# main.net
KiCad netlist of a schematic drawn in Altium Designer
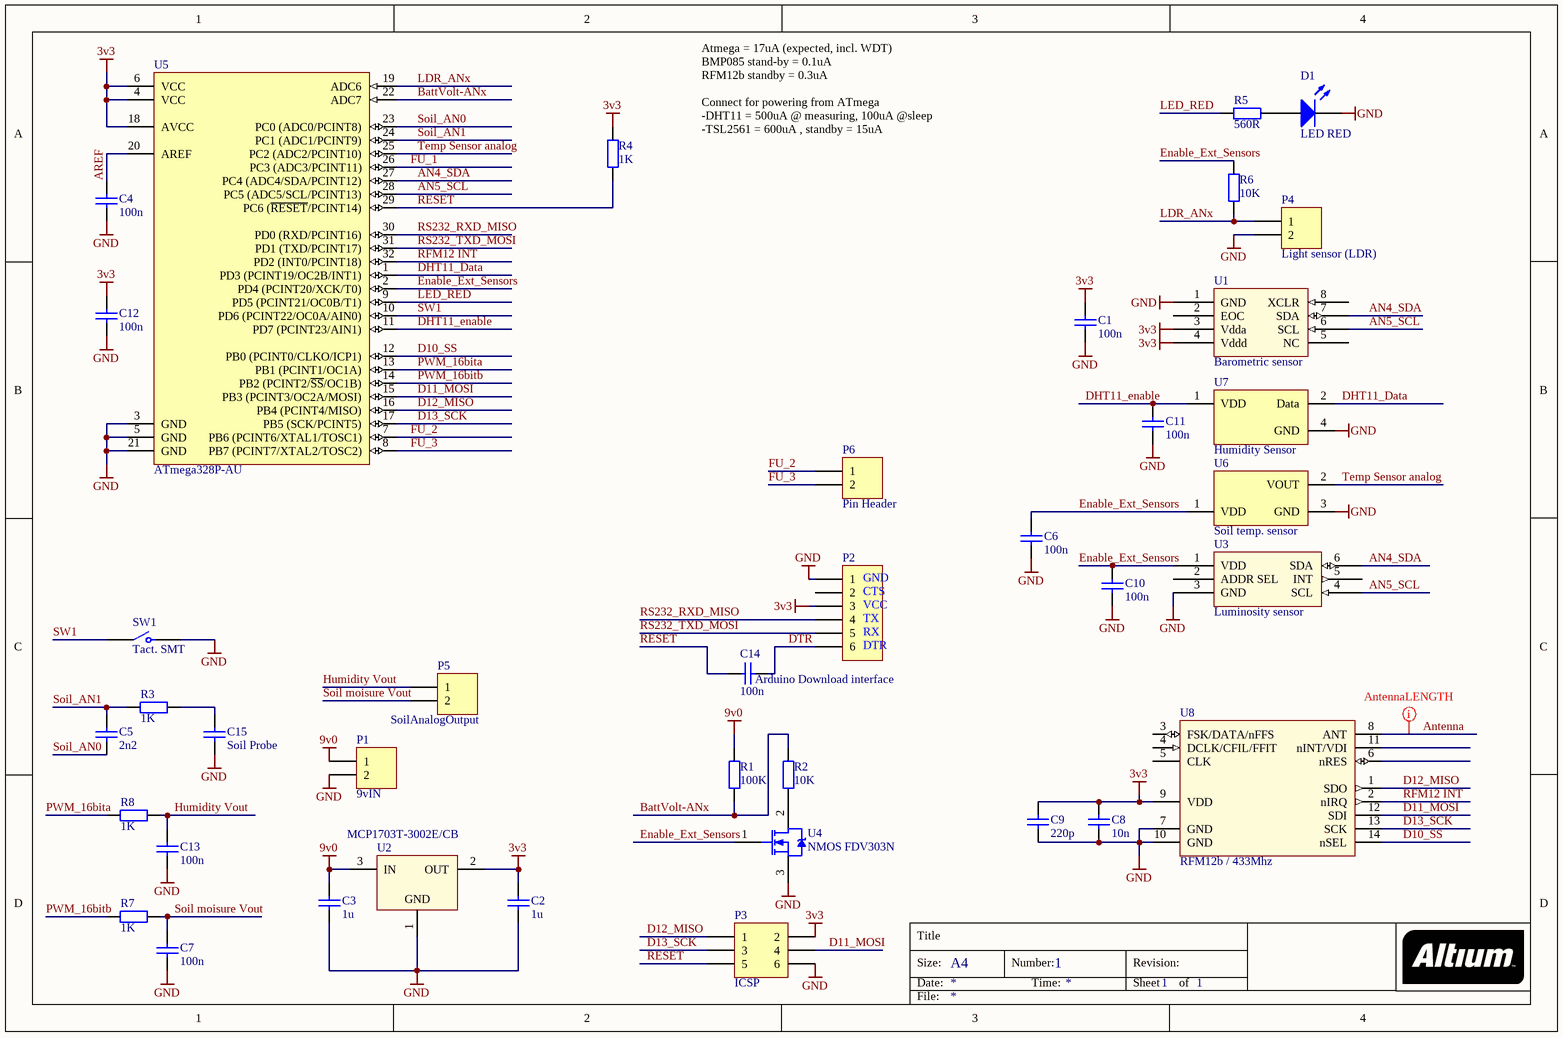
[diagram p0: main.SchDoc]

(export (version "E")
  (design (tool "Eeschema 10.0.6"))
  (components
    (comp (ref "C1") (value "100n") (footprint "C0805") (libsource (lib "OurDb") (part "cap_NonPolar")))
    (comp (ref "C2") (value "1u") (footprint "C0805") (libsource (lib "OurDb") (part "cap_NonPolar")))
    (comp (ref "C3") (value "1u") (footprint "C0805") (libsource (lib "OurDb") (part "cap_NonPolar")))
    (comp (ref "C4") (value "100n") (footprint "C0805") (libsource (lib "OurDb") (part "cap_NonPolar")))
    (comp (ref "C5") (value "2n2") (footprint "C0805") (libsource (lib "OurDb") (part "cap_NonPolar")))
    (comp (ref "C6") (value "100n") (footprint "C0805") (libsource (lib "OurDb") (part "cap_NonPolar")))
    (comp (ref "C7") (value "100n") (footprint "C0805") (libsource (lib "OurDb") (part "cap_NonPolar")))
    (comp (ref "C8") (value "10n") (footprint "C0805") (libsource (lib "OurDb") (part "cap_NonPolar")))
    (comp (ref "C9") (value "220p") (footprint "C0805") (libsource (lib "OurDb") (part "cap_NonPolar")))
    (comp (ref "C10") (value "100n") (footprint "C0805") (libsource (lib "OurDb") (part "cap_NonPolar")))
    (comp (ref "C11") (value "100n") (footprint "C0805") (libsource (lib "OurDb") (part "cap_NonPolar")))
    (comp (ref "C12") (value "100n") (footprint "C0805") (libsource (lib "OurDb") (part "cap_NonPolar")))
    (comp (ref "C13") (value "100n") (footprint "C0805") (libsource (lib "OurDb") (part "cap_NonPolar")))
    (comp (ref "C14") (value "100n") (footprint "C0805") (libsource (lib "OurDb") (part "cap_NonPolar")))
    (comp (ref "C15")
      (value "Soil Probe")
      (footprint "C0805")
      (fields (field (name "PART NUMBER") "18p"))
      (libsource (lib "OurDb") (part "cap_NonPolar"))
    )
    (comp (ref "D1")
      (value "LED RED")
      (footprint "LED-3mm")
      (description "LED, Surface Mount LED Indicator")
      (fields (field (name "PART NUMBER") "Red-3mm"))
      (libsource (lib "OurDb") (part "LED_SINGLE"))
    )
    (comp (ref "P1")
      (value "9vIN")
      (footprint "PH1x2_2.54")
      (description "Con1x2")
      (fields (field (name "PART NUMBER") "PH1x2"))
      (libsource (lib "OurDb") (part "Con1x2"))
    )
    (comp (ref "P2")
      (value "Arduino Download interface")
      (footprint "PH1x6_2.54")
      (description "Con1x6")
      (fields (field (name "PART NUMBER") "PH1x6"))
      (libsource (lib "OurDb") (part "Con1x6"))
    )
    (comp (ref "P3")
      (value "ICSP")
      (footprint "PH2x3_2.54")
      (description "Header, 3-Pin, Dual row")
      (fields (field (name "PART NUMBER") "PH2x3"))
      (libsource (lib "OurDb") (part "Con2x3"))
    )
    (comp (ref "P4")
      (value "Light sensor (LDR)")
      (footprint "PH1x2_2.54")
      (description "Con1x2")
      (fields (field (name "PART NUMBER") "PH1x2"))
      (libsource (lib "OurDb") (part "Con1x2"))
    )
    (comp (ref "P5")
      (value "SoilAnalogOutput")
      (footprint "PH1x2_2.54")
      (description "Con1x2")
      (fields (field (name "PART NUMBER") "PH1x2"))
      (libsource (lib "OurDb") (part "Con1x2"))
    )
    (comp (ref "P6")
      (value "Pin Header")
      (footprint "PH1x2_2.54")
      (description "Con1x2")
      (fields (field (name "PART NUMBER") "PH1x2") (field (name "AUTHOR") "Willy Pietersz"))
      (libsource (lib "OurDb") (part "Con1x2"))
    )
    (comp (ref "R1")
      (value "RESISTOR")
      (footprint "R0805")
      (description "Resistor")
      (fields (field (name "PART NUMBER") "100K") (field (name "PUBLISHER") "Altium Limited"))
      (libsource (lib "") (part "RESISTOR_1"))
    )
    (comp (ref "R2")
      (value "RESISTOR")
      (footprint "R0805")
      (description "Resistor")
      (fields (field (name "PART NUMBER") "10K") (field (name "PUBLISHER") "Altium Limited"))
      (libsource (lib "OurDb") (part "RESISTOR"))
    )
    (comp (ref "R3")
      (value "RESISTOR")
      (footprint "R0805")
      (description "Resistor")
      (fields (field (name "PART NUMBER") "1K") (field (name "PUBLISHER") "Altium Limited"))
      (libsource (lib "") (part "RESISTOR_2"))
    )
    (comp (ref "R4")
      (value "RESISTOR")
      (footprint "R0805")
      (description "Resistor")
      (fields (field (name "PART NUMBER") "1K") (field (name "PUBLISHER") "Altium Limited"))
      (libsource (lib "") (part "RESISTOR_1"))
    )
    (comp (ref "R5")
      (value "RESISTOR")
      (footprint "R0805")
      (description "Resistor")
      (fields (field (name "PART NUMBER") "560R") (field (name "PUBLISHER") "Altium Limited"))
      (libsource (lib "") (part "RESISTOR_3"))
    )
    (comp (ref "R6")
      (value "RESISTOR")
      (footprint "R0805")
      (description "Resistor")
      (fields (field (name "PART NUMBER") "10K") (field (name "PUBLISHER") "Altium Limited"))
      (libsource (lib "") (part "RESISTOR_1"))
    )
    (comp (ref "R7")
      (value "RESISTOR")
      (footprint "R0805")
      (description "Resistor")
      (fields (field (name "PART NUMBER") "1K") (field (name "PUBLISHER") "Altium Limited"))
      (libsource (lib "") (part "RESISTOR_2"))
    )
    (comp (ref "R8")
      (value "RESISTOR")
      (footprint "R0805")
      (description "Resistor")
      (fields (field (name "PART NUMBER") "1K") (field (name "PUBLISHER") "Altium Limited"))
      (libsource (lib "") (part "RESISTOR_2"))
    )
    (comp (ref "SW1")
      (value "Tact. SMT")
      (footprint "Switch TACT 3.5*6")
      (description "Switch")
      (fields
        (field (name "PART NUMBER") "Pushbutton TACT mini 3.5x6")
        (field (name "VOLTAGE") "42")
        (field (name "AUTHOR") "Willem Pietersz")
      )
      (libsource (lib "OurDb") (part "SW-TACT 2p"))
    )
    (comp (ref "U1")
      (value "Barometric sensor")
      (footprint "BMP085")
      (description "Sensor, Barometric")
      (fields (field (name "PART NUMBER") "BMP085"))
      (libsource (lib "OurDb") (part "BMP085"))
    )
    (comp (ref "U2")
      (value "MCP1703T")
      (footprint "SOT23")
      (description "Regulator, 5v")
      (fields (field (name "PART NUMBER") "MCP1703T-3002E/CB"))
      (libsource (lib "OurDb") (part "AMS1117"))
    )
    (comp (ref "U3")
      (value "Luminosity sensor")
      (footprint "TSL2561")
      (description "Sensor, Illumination")
      (fields (field (name "PART NUMBER") "TSL2561"))
      (libsource (lib "OurDb") (part "TSL2561"))
    )
    (comp (ref "U4")
      (value "NMOS FDV303N")
      (footprint "SOT-23-FET")
      (description "Transistor")
      (fields (field (name "PART NUMBER") "FDV303N"))
      (libsource (lib "OurDb") (part "NMOS"))
    )
    (comp (ref "U5")
      (value "ATmega328P-AU")
      (footprint "atmel_32A_N")
      (fields (field (name "PUBLISHER") "Altium Limited"))
      (libsource (lib "AltiumDatabaseSelection") (part "ATmega328P-AU"))
    )
    (comp (ref "U6")
      (value "Soil temp. sensor")
      (footprint "SOT-23-TT3_M")
      (description "Low-Power Linear Active Thermistor IC, 3-Pin SOT-23, Extended Temperature, Tape and Reel")
      (fields (field (name "PART NUMBER") "MCP9700AT-E/TT"))
      (libsource (lib "OurDb") (part "MCP9700AT-E/TT"))
    )
    (comp (ref "U7")
      (value "Humidity Sensor")
      (footprint "DHTXX")
      (description "Humidity / Temp Sensor")
      (fields (field (name "PART NUMBER") "DHT11"))
      (libsource (lib "OurDb") (part "DHT11"))
    )
    (comp (ref "U8")
      (value "RFM12b / 433Mhz")
      (footprint "RFM12_dev")
      (description "Wireless, Transceiver")
      (fields (field (name "PART NUMBER") "RFM12b"))
      (libsource (lib "OurDb") (part "RFM12B"))
    )
  )
  (nets
    (net (code "1") (name "/AN4_SDA") (class "Default")
      (node (ref "U1") (pin "7") (pinfunction "SDA_7") (pintype "bidirectional"))
      (node (ref "U3") (pin "6") (pinfunction "SDA_6") (pintype "bidirectional"))
      (node (ref "U5") (pin "27") (pinfunction "PC4_(ADC4/SDA/PCINT12)_27") (pintype "bidirectional"))
    )
    (net (code "2") (name "/AN5_SCL") (class "Default")
      (node (ref "U1") (pin "6") (pinfunction "SCL_6") (pintype "input"))
      (node (ref "U3") (pin "4") (pinfunction "SCL_4") (pintype "input"))
      (node (ref "U5") (pin "28") (pinfunction "PC5_(ADC5/SCL/PCINT13)_28") (pintype "bidirectional"))
    )
    (net (code "3") (name "/AREF") (class "Default")
      (node (ref "C4") (pin "2") (pinfunction "2_2") (pintype "passive"))
      (node (ref "U5") (pin "20") (pinfunction "AREF_20") (pintype "passive"))
    )
    (net (code "4") (name "/Antenna") (class "Default")
      (node (ref "U8") (pin "8") (pinfunction "ANT_8") (pintype "power_in"))
    )
    (net (code "5") (name "/BattVolt-ANx") (class "Default")
      (node (ref "R1") (pin "2") (pinfunction "2_2") (pintype "passive"))
      (node (ref "R2") (pin "2") (pinfunction "2_2") (pintype "passive"))
      (node (ref "U5") (pin "22") (pinfunction "ADC7_22") (pintype "input"))
    )
    (net (code "6") (name "/D10_SS") (class "Default")
      (node (ref "U5") (pin "12") (pinfunction "PB0_(PCINT0/CLKO/ICP1)_12") (pintype "bidirectional"))
      (node (ref "U8") (pin "14") (pinfunction "nSEL_14") (pintype "passive"))
    )
    (net (code "7") (name "/D11_MOSI") (class "Default")
      (node (ref "P3") (pin "4") (pinfunction "4_4") (pintype "passive"))
      (node (ref "U5") (pin "15") (pinfunction "PB3_(PCINT3/OC2A/MOSI)_15") (pintype "bidirectional"))
      (node (ref "U8") (pin "12") (pinfunction "SDI_12") (pintype "passive"))
    )
    (net (code "8") (name "/D12_MISO") (class "Default")
      (node (ref "P3") (pin "1") (pinfunction "1_1") (pintype "passive"))
      (node (ref "U5") (pin "16") (pinfunction "PB4_(PCINT4/MISO)_16") (pintype "bidirectional"))
      (node (ref "U8") (pin "1") (pinfunction "SDO_1") (pintype "output"))
    )
    (net (code "9") (name "/D13_SCK") (class "Default")
      (node (ref "P3") (pin "3") (pinfunction "3_3") (pintype "passive"))
      (node (ref "U5") (pin "17") (pinfunction "PB5_(SCK/PCINT5)_17") (pintype "bidirectional"))
      (node (ref "U8") (pin "13") (pinfunction "SCK_13") (pintype "passive"))
    )
    (net (code "10") (name "/DHT11_Data") (class "Default")
      (node (ref "U5") (pin "1") (pinfunction "PD3_(PCINT19/OC2B/INT1)_1") (pintype "bidirectional"))
      (node (ref "U7") (pin "2") (pinfunction "Data_2") (pintype "power_in"))
    )
    (net (code "11") (name "/DHT11_enable") (class "Default")
      (node (ref "C11") (pin "2") (pinfunction "2_2") (pintype "passive"))
      (node (ref "U5") (pin "11") (pinfunction "PD7_(PCINT23/AIN1)_11") (pintype "bidirectional"))
      (node (ref "U7") (pin "1") (pinfunction "VDD_1") (pintype "power_in"))
    )
    (net (code "12") (name "/DTR") (class "Default")
      (node (ref "C14") (pin "2") (pinfunction "2_2") (pintype "passive"))
      (node (ref "P2") (pin "6") (pinfunction "6_6") (pintype "passive"))
    )
    (net (code "13") (name "/Enable_Ext_Sensors") (class "Default")
      (node (ref "C10") (pin "2") (pinfunction "2_2") (pintype "passive"))
      (node (ref "C6") (pin "2") (pinfunction "2_2") (pintype "passive"))
      (node (ref "R6") (pin "1") (pinfunction "1_1") (pintype "passive"))
      (node (ref "U3") (pin "1") (pinfunction "VDD_1") (pintype "power_in"))
      (node (ref "U4") (pin "1") (pinfunction "G_1") (pintype "passive"))
      (node (ref "U5") (pin "2") (pinfunction "PD4_(PCINT20/XCK/T0)_2") (pintype "bidirectional"))
      (node (ref "U6") (pin "1") (pinfunction "VDD_1") (pintype "power_in"))
    )
    (net (code "14") (name "/FU_1") (class "Default")
      (node (ref "U5") (pin "26") (pinfunction "PC3_(ADC3/PCINT11)_26") (pintype "bidirectional"))
    )
    (net (code "15") (name "/FU_2") (class "Default")
      (node (ref "P6") (pin "1") (pinfunction "1_1") (pintype "passive"))
      (node (ref "U5") (pin "7") (pinfunction "PB6_(PCINT6/XTAL1/TOSC1)_7") (pintype "bidirectional"))
    )
    (net (code "16") (name "/FU_3") (class "Default")
      (node (ref "P6") (pin "2") (pinfunction "2_2") (pintype "passive"))
      (node (ref "U5") (pin "8") (pinfunction "PB7_(PCINT7/XTAL2/TOSC2)_8") (pintype "bidirectional"))
    )
    (net (code "17") (name "/Humidity Vout") (class "Default")
      (node (ref "C13") (pin "2") (pinfunction "2_2") (pintype "passive"))
      (node (ref "P5") (pin "1") (pinfunction "1_1") (pintype "passive"))
      (node (ref "R8") (pin "1") (pinfunction "1_1") (pintype "passive"))
    )
    (net (code "18") (name "/LDR_ANx") (class "Default")
      (node (ref "P4") (pin "1") (pinfunction "1_1") (pintype "passive"))
      (node (ref "R6") (pin "2") (pinfunction "2_2") (pintype "passive"))
      (node (ref "U5") (pin "19") (pinfunction "ADC6_19") (pintype "input"))
    )
    (net (code "19") (name "/LED_RED") (class "Default")
      (node (ref "R5") (pin "1") (pinfunction "1_1") (pintype "passive"))
      (node (ref "U5") (pin "9") (pinfunction "PD5_(PCINT21/OC0B/T1)_9") (pintype "bidirectional"))
    )
    (net (code "20") (name "/PWM_16bita") (class "Default")
      (node (ref "R8") (pin "2") (pinfunction "2_2") (pintype "passive"))
      (node (ref "U5") (pin "13") (pinfunction "PB1_(PCINT1/OC1A)_13") (pintype "bidirectional"))
    )
    (net (code "21") (name "/PWM_16bitb") (class "Default")
      (node (ref "R7") (pin "2") (pinfunction "2_2") (pintype "passive"))
      (node (ref "U5") (pin "14") (pinfunction "PB2_(PCINT2/~{SS}/OC1B)_14") (pintype "bidirectional"))
    )
    (net (code "22") (name "/RESET") (class "Default")
      (node (ref "C14") (pin "1") (pinfunction "1_1") (pintype "passive"))
      (node (ref "P3") (pin "5") (pinfunction "5_5") (pintype "passive"))
      (node (ref "R4") (pin "2") (pinfunction "2_2") (pintype "passive"))
      (node (ref "U5") (pin "29") (pinfunction "PC6_(~{RESET}/PCINT14)_29") (pintype "bidirectional"))
    )
    (net (code "23") (name "/RFM12 INT") (class "Default")
      (node (ref "U5") (pin "32") (pinfunction "PD2_(INT0/PCINT18)_32") (pintype "bidirectional"))
      (node (ref "U8") (pin "2") (pinfunction "nIRQ_2") (pintype "output"))
    )
    (net (code "24") (name "/RS232_RXD_MISO") (class "Default")
      (node (ref "P2") (pin "4") (pinfunction "4_4") (pintype "passive"))
      (node (ref "U5") (pin "30") (pinfunction "PD0_(RXD/PCINT16)_30") (pintype "bidirectional"))
    )
    (net (code "25") (name "/RS232_TXD_MOSI") (class "Default")
      (node (ref "P2") (pin "5") (pinfunction "5_5") (pintype "passive"))
      (node (ref "U5") (pin "31") (pinfunction "PD1_(TXD/PCINT17)_31") (pintype "bidirectional"))
    )
    (net (code "26") (name "/SW1") (class "Default")
      (node (ref "SW1") (pin "1") (pintype "passive"))
      (node (ref "U5") (pin "10") (pinfunction "PD6_(PCINT22/OC0A/AIN0)_10") (pintype "bidirectional"))
    )
    (net (code "27") (name "/Soil moisure Vout") (class "Default")
      (node (ref "C7") (pin "2") (pinfunction "2_2") (pintype "passive"))
      (node (ref "P5") (pin "2") (pinfunction "2_2") (pintype "passive"))
      (node (ref "R7") (pin "1") (pinfunction "1_1") (pintype "passive"))
    )
    (net (code "28") (name "/Soil_AN0") (class "Default")
      (node (ref "C5") (pin "1") (pinfunction "1_1") (pintype "passive"))
      (node (ref "U5") (pin "23") (pinfunction "PC0_(ADC0/PCINT8)_23") (pintype "bidirectional"))
    )
    (net (code "29") (name "/Soil_AN1") (class "Default")
      (node (ref "C5") (pin "2") (pinfunction "2_2") (pintype "passive"))
      (node (ref "R3") (pin "2") (pinfunction "2_2") (pintype "passive"))
      (node (ref "U5") (pin "24") (pinfunction "PC1_(ADC1/PCINT9)_24") (pintype "bidirectional"))
    )
    (net (code "30") (name "/Temp Sensor analog") (class "Default")
      (node (ref "U5") (pin "25") (pinfunction "PC2_(ADC2/PCINT10)_25") (pintype "bidirectional"))
      (node (ref "U6") (pin "2") (pinfunction "VOUT_2") (pintype "power_in"))
    )
    (net (code "31") (name "3v3") (class "Default")
      (node (ref "C1") (pin "2") (pinfunction "2_2") (pintype "passive"))
      (node (ref "C12") (pin "2") (pinfunction "2_2") (pintype "passive"))
      (node (ref "C2") (pin "2") (pinfunction "2_2") (pintype "passive"))
      (node (ref "C8") (pin "2") (pinfunction "2_2") (pintype "passive"))
      (node (ref "C9") (pin "2") (pinfunction "2_2") (pintype "passive"))
      (node (ref "P2") (pin "3") (pinfunction "3_3") (pintype "passive"))
      (node (ref "P3") (pin "2") (pinfunction "2_2") (pintype "passive"))
      (node (ref "R4") (pin "1") (pinfunction "1_1") (pintype "passive"))
      (node (ref "U1") (pin "3") (pinfunction "Vdda_3") (pintype "power_in"))
      (node (ref "U1") (pin "4") (pinfunction "Vddd_4") (pintype "power_in"))
      (node (ref "U2") (pin "2") (pinfunction "OUT_2") (pintype "power_in"))
      (node (ref "U5") (pin "18") (pinfunction "AVCC_18") (pintype "power_in"))
      (node (ref "U5") (pin "4") (pinfunction "VCC_4") (pintype "power_in"))
      (node (ref "U5") (pin "6") (pinfunction "VCC_6") (pintype "power_in"))
      (node (ref "U8") (pin "9") (pinfunction "VDD_9") (pintype "power_in"))
    )
    (net (code "32") (name "9v0") (class "Default")
      (node (ref "C3") (pin "2") (pinfunction "2_2") (pintype "passive"))
      (node (ref "P1") (pin "1") (pinfunction "1_1") (pintype "passive"))
      (node (ref "R1") (pin "1") (pinfunction "1_1") (pintype "passive"))
      (node (ref "U2") (pin "3") (pinfunction "IN_3") (pintype "passive"))
    )
    (net (code "33") (name "GND") (class "Default")
      (node (ref "C1") (pin "1") (pinfunction "1_1") (pintype "passive"))
      (node (ref "C10") (pin "1") (pinfunction "1_1") (pintype "passive"))
      (node (ref "C11") (pin "1") (pinfunction "1_1") (pintype "passive"))
      (node (ref "C12") (pin "1") (pinfunction "1_1") (pintype "passive"))
      (node (ref "C13") (pin "1") (pinfunction "1_1") (pintype "passive"))
      (node (ref "C15") (pin "1") (pinfunction "1_1") (pintype "passive"))
      (node (ref "C2") (pin "1") (pinfunction "1_1") (pintype "passive"))
      (node (ref "C3") (pin "1") (pinfunction "1_1") (pintype "passive"))
      (node (ref "C4") (pin "1") (pinfunction "1_1") (pintype "passive"))
      (node (ref "C6") (pin "1") (pinfunction "1_1") (pintype "passive"))
      (node (ref "C7") (pin "1") (pinfunction "1_1") (pintype "passive"))
      (node (ref "C8") (pin "1") (pinfunction "1_1") (pintype "passive"))
      (node (ref "C9") (pin "1") (pinfunction "1_1") (pintype "passive"))
      (node (ref "D1") (pin "2") (pinfunction "K_2") (pintype "passive"))
      (node (ref "P1") (pin "2") (pinfunction "2_2") (pintype "passive"))
      (node (ref "P2") (pin "1") (pinfunction "1_1") (pintype "passive"))
      (node (ref "P3") (pin "6") (pinfunction "6_6") (pintype "passive"))
      (node (ref "P4") (pin "2") (pinfunction "2_2") (pintype "passive"))
      (node (ref "SW1") (pin "2") (pintype "passive"))
      (node (ref "U1") (pin "1") (pinfunction "GND_1") (pintype "power_in"))
      (node (ref "U2") (pin "1") (pinfunction "GND_1") (pintype "passive"))
      (node (ref "U3") (pin "3") (pinfunction "GND_3") (pintype "power_in"))
      (node (ref "U4") (pin "3") (pinfunction "S_3") (pintype "passive"))
      (node (ref "U5") (pin "21") (pinfunction "GND_21") (pintype "power_in"))
      (node (ref "U5") (pin "3") (pinfunction "GND_3") (pintype "power_in"))
      (node (ref "U5") (pin "5") (pinfunction "GND_5") (pintype "power_in"))
      (node (ref "U6") (pin "3") (pinfunction "GND_3") (pintype "power_in"))
      (node (ref "U7") (pin "4") (pinfunction "GND_4") (pintype "power_in"))
      (node (ref "U8") (pin "10") (pinfunction "GND_10") (pintype "power_in"))
      (node (ref "U8") (pin "7") (pinfunction "GND_7") (pintype "power_in"))
    )
    (net (code "34") (name "Net-(C15-Pad2)") (class "Default")
      (node (ref "C15") (pin "2") (pinfunction "2_2") (pintype "passive"))
      (node (ref "R3") (pin "1") (pinfunction "1_1") (pintype "passive"))
    )
    (net (code "35") (name "Net-(D1-A)") (class "Default")
      (node (ref "D1") (pin "1") (pinfunction "A_1") (pintype "passive"))
      (node (ref "R5") (pin "2") (pinfunction "2_2") (pintype "passive"))
    )
    (net (code "36") (name "Net-(U4-D)") (class "Default")
      (node (ref "R2") (pin "1") (pinfunction "1_1") (pintype "passive"))
      (node (ref "U4") (pin "2") (pinfunction "D_2") (pintype "passive"))
    )
    (net (code "37") (name "unconnected-(P2-Pad2)") (class "Default")
      (node (ref "P2") (pin "2") (pinfunction "2_2") (pintype "passive"))
    )
    (net (code "38") (name "unconnected-(U1-EOC-Pad2)") (class "Default")
      (node (ref "U1") (pin "2") (pinfunction "EOC_2") (pintype "passive"))
    )
    (net (code "39") (name "unconnected-(U1-NC-Pad5)") (class "Default")
      (node (ref "U1") (pin "5") (pinfunction "NC_5") (pintype "passive"))
    )
    (net (code "40") (name "unconnected-(U1-XCLR-Pad8)") (class "Default")
      (node (ref "U1") (pin "8") (pinfunction "XCLR_8") (pintype "input"))
    )
    (net (code "41") (name "unconnected-(U3-ADDR_SEL-Pad2)") (class "Default")
      (node (ref "U3") (pin "2") (pinfunction "ADDR_SEL_2") (pintype "passive"))
    )
    (net (code "42") (name "unconnected-(U3-INT-Pad5)") (class "Default")
      (node (ref "U3") (pin "5") (pinfunction "INT_5") (pintype "output"))
    )
    (net (code "43") (name "unconnected-(U8-CLK-Pad5)") (class "Default")
      (node (ref "U8") (pin "5") (pinfunction "CLK_5") (pintype "power_in"))
    )
    (net (code "44") (name "unconnected-(U8-DCLK{slash}CFIL{slash}FFIT-Pad4)") (class "Default")
      (node (ref "U8") (pin "4") (pinfunction "DCLK/CFIL/FFIT_4") (pintype "input"))
    )
    (net (code "45") (name "unconnected-(U8-FSK{slash}DATA{slash}nFFS-Pad3)") (class "Default")
      (node (ref "U8") (pin "3") (pinfunction "FSK/DATA/nFFS_3") (pintype "bidirectional"))
    )
    (net (code "46") (name "unconnected-(U8-nINT{slash}VDI-Pad11)") (class "Default")
      (node (ref "U8") (pin "11") (pinfunction "nINT/VDI_11") (pintype "passive"))
    )
    (net (code "47") (name "unconnected-(U8-nRES-Pad6)") (class "Default")
      (node (ref "U8") (pin "6") (pinfunction "nRES_6") (pintype "bidirectional"))
    )
  )
)
